# gadgeteer_HD44780.net
KiCad netlist of a schematic drawn in EAGLE
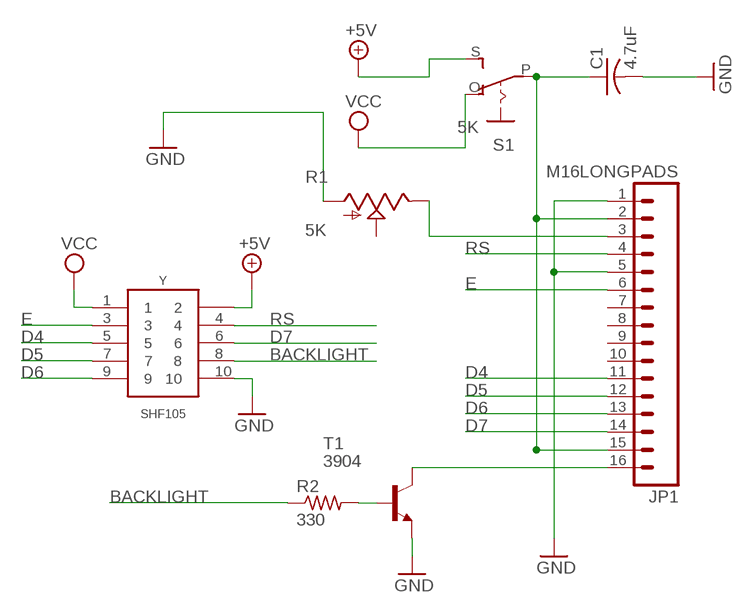
[diagram p0: schematic, sheet 1]

(export (version "E")
  (design (tool "Eeschema 10.0.6"))
  (components
    (comp (ref "C1")
      (value "4.7uF")
      (footprint "eagle-import:C1206K")
      (libsource (lib "eagle-import") (part "C-USC1206K"))
    )
    (comp (ref "JP1")
      (value "M16LONGPADS")
      (footprint "eagle-import:1X16_LONGPADS")
      (libsource (lib "eagle-import") (part "M16LONGPADS"))
    )
    (comp (ref "R1")
      (value "5K")
      (footprint "eagle-import:BOURNS-TC33X")
      (libsource (lib "eagle-import") (part "POTENTIOMETER"))
    )
    (comp (ref "R2")
      (value "330")
      (footprint "eagle-import:R0603")
      (libsource (lib "eagle-import") (part "R-US_R0603"))
    )
    (comp (ref "S1")
      (value "5K")
      (footprint "eagle-import:EG1218")
      (libsource (lib "eagle-import") (part "EG1218S"))
    )
    (comp (ref "T1")
      (value "3904")
      (footprint "eagle-import:SOT23-BEC")
      (libsource (lib "eagle-import") (part "-NPN-SOT23-BECMMBT3904LT1"))
    )
    (comp (ref "Y")
      (value "SHF105")
      (footprint "eagle-import:GAD_PAC_SMD")
      (libsource (lib "eagle-import") (part "SHF105"))
    )
  )
  (nets
    (net (code "1") (name "+5V") (class "Default")
      (node (ref "S1") (pin "S") (pinfunction "S_S") (pintype "passive"))
      (node (ref "Y") (pin "2") (pinfunction "2_2") (pintype "passive"))
    )
    (net (code "2") (name "/BACKLIGHT") (class "Default")
      (node (ref "R2") (pin "1") (pinfunction "1_1") (pintype "passive"))
      (node (ref "Y") (pin "8") (pinfunction "8_8") (pintype "passive"))
    )
    (net (code "3") (name "/D4") (class "Default")
      (node (ref "JP1") (pin "11") (pinfunction "11_11") (pintype "passive"))
      (node (ref "Y") (pin "5") (pinfunction "5_5") (pintype "passive"))
    )
    (net (code "4") (name "/D5") (class "Default")
      (node (ref "JP1") (pin "12") (pinfunction "12_12") (pintype "passive"))
      (node (ref "Y") (pin "7") (pinfunction "7_7") (pintype "passive"))
    )
    (net (code "5") (name "/D6") (class "Default")
      (node (ref "JP1") (pin "13") (pinfunction "13_13") (pintype "passive"))
      (node (ref "Y") (pin "9") (pinfunction "9_9") (pintype "passive"))
    )
    (net (code "6") (name "/D7") (class "Default")
      (node (ref "JP1") (pin "14") (pinfunction "14_14") (pintype "passive"))
      (node (ref "Y") (pin "6") (pinfunction "6_6") (pintype "passive"))
    )
    (net (code "7") (name "/E") (class "Default")
      (node (ref "JP1") (pin "6") (pinfunction "6_6") (pintype "passive"))
      (node (ref "Y") (pin "3") (pinfunction "3_3") (pintype "passive"))
    )
    (net (code "8") (name "/RS") (class "Default")
      (node (ref "JP1") (pin "4") (pinfunction "4_4") (pintype "passive"))
      (node (ref "Y") (pin "4") (pinfunction "4_4") (pintype "passive"))
    )
    (net (code "9") (name "GND") (class "Default")
      (node (ref "C1") (pin "2") (pinfunction "2_2") (pintype "passive"))
      (node (ref "JP1") (pin "1") (pinfunction "1_1") (pintype "passive"))
      (node (ref "JP1") (pin "5") (pinfunction "5_5") (pintype "passive"))
      (node (ref "R1") (pin "1") (pinfunction "A_1") (pintype "passive"))
      (node (ref "T1") (pin "E") (pinfunction "E_E") (pintype "passive"))
      (node (ref "Y") (pin "10") (pinfunction "10_10") (pintype "passive"))
    )
    (net (code "10") (name "Net-(C1-Pad1)") (class "Default")
      (node (ref "C1") (pin "1") (pinfunction "1_1") (pintype "passive"))
      (node (ref "JP1") (pin "15") (pinfunction "15_15") (pintype "passive"))
      (node (ref "JP1") (pin "2") (pinfunction "2_2") (pintype "passive"))
      (node (ref "S1") (pin "P") (pinfunction "P_P") (pintype "passive"))
    )
    (net (code "11") (name "Net-(JP1-Pad16)") (class "Default")
      (node (ref "JP1") (pin "16") (pinfunction "16_16") (pintype "passive"))
      (node (ref "T1") (pin "C") (pinfunction "C_C") (pintype "passive"))
    )
    (net (code "12") (name "Net-(R1-E)") (class "Default")
      (node (ref "JP1") (pin "3") (pinfunction "3_3") (pintype "passive"))
      (node (ref "R1") (pin "3") (pinfunction "E_3") (pintype "passive"))
    )
    (net (code "13") (name "Net-(R2-Pad2)") (class "Default")
      (node (ref "R2") (pin "2") (pinfunction "2_2") (pintype "passive"))
      (node (ref "T1") (pin "B") (pinfunction "B_B") (pintype "passive"))
    )
    (net (code "14") (name "VCC") (class "Default")
      (node (ref "S1") (pin "O") (pinfunction "O_O") (pintype "passive"))
      (node (ref "Y") (pin "1") (pinfunction "1_1") (pintype "passive"))
    )
    (net (code "15") (name "unconnected-(JP1-Pad7)") (class "Default")
      (node (ref "JP1") (pin "7") (pinfunction "7_7") (pintype "passive"))
    )
    (net (code "16") (name "unconnected-(JP1-Pad8)") (class "Default")
      (node (ref "JP1") (pin "8") (pinfunction "8_8") (pintype "passive"))
    )
    (net (code "17") (name "unconnected-(JP1-Pad9)") (class "Default")
      (node (ref "JP1") (pin "9") (pinfunction "9_9") (pintype "passive"))
    )
    (net (code "18") (name "unconnected-(JP1-Pad10)") (class "Default")
      (node (ref "JP1") (pin "10") (pinfunction "10_10") (pintype "passive"))
    )
    (net (code "19") (name "unconnected-(R1-S-Pad2)") (class "Default")
      (node (ref "R1") (pin "2") (pinfunction "S_2") (pintype "passive"))
    )
  )
)
